# ADP151-1V8.net
KiCad netlist of a schematic drawn in Altium Designer
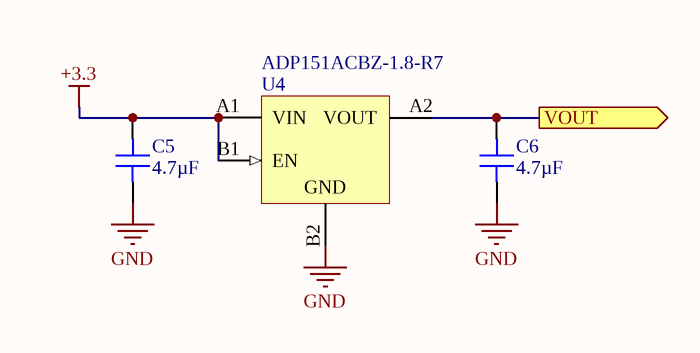
[diagram p0: ADP151-1V8.SchDoc]

(export (version "E")
  (design (tool "Eeschema 10.0.6"))
  (components
    (comp (ref "C5")
      (value "4.7µF")
      (footprint "CAP 0402_1005")
      (description "CAP CER 4.7UF 10V X5R 0402")
      (fields
        (field (name "PART NUMBER") "GRM155R61A475MEAAD")
        (field (name "MANUFACTURER") "Murata Electronics")
      )
      (libsource (lib "Celestial Altium Library - altium_library") (part "Capacitor"))
    )
    (comp (ref "C6")
      (value "4.7µF")
      (footprint "CAP 0402_1005")
      (description "CAP CER 4.7UF 10V X5R 0402")
      (fields
        (field (name "PART NUMBER") "GRM155R61A475MEAAD")
        (field (name "MANUFACTURER") "Murata Electronics")
      )
      (libsource (lib "Celestial Altium Library - altium_library") (part "Capacitor"))
    )
    (comp (ref "U4")
      (value "ADP151ACBZ-1.8-R7")
      (footprint "ADI-CB-4-3")
      (fields (field (name "MANUFACTURER") "Analog Devices"))
      (libsource (lib "Altium Content Vault") (part "ADI-ADP151-CB-4-3"))
    )
  )
  (nets
    (net (code "1") (name "+3.3") (class "Default")
      (node (ref "C5") (pin "2") (pinfunction "2_2") (pintype "passive"))
      (node (ref "U4") (pin "A1") (pinfunction "VIN_A1") (pintype "power_in"))
      (node (ref "U4") (pin "B1") (pinfunction "EN_B1") (pintype "input"))
    )
    (net (code "2") (name "/VOUT") (class "Default")
      (node (ref "C6") (pin "2") (pinfunction "2_2") (pintype "passive"))
      (node (ref "U4") (pin "A2") (pinfunction "VOUT_A2") (pintype "power_in"))
    )
    (net (code "3") (name "GND") (class "Default")
      (node (ref "C5") (pin "1") (pinfunction "1_1") (pintype "passive"))
      (node (ref "C6") (pin "1") (pinfunction "1_1") (pintype "passive"))
      (node (ref "U4") (pin "B2") (pinfunction "GND_B2") (pintype "power_in"))
    )
  )
)
